# robot.net
KiCad netlist of a schematic drawn in EAGLE
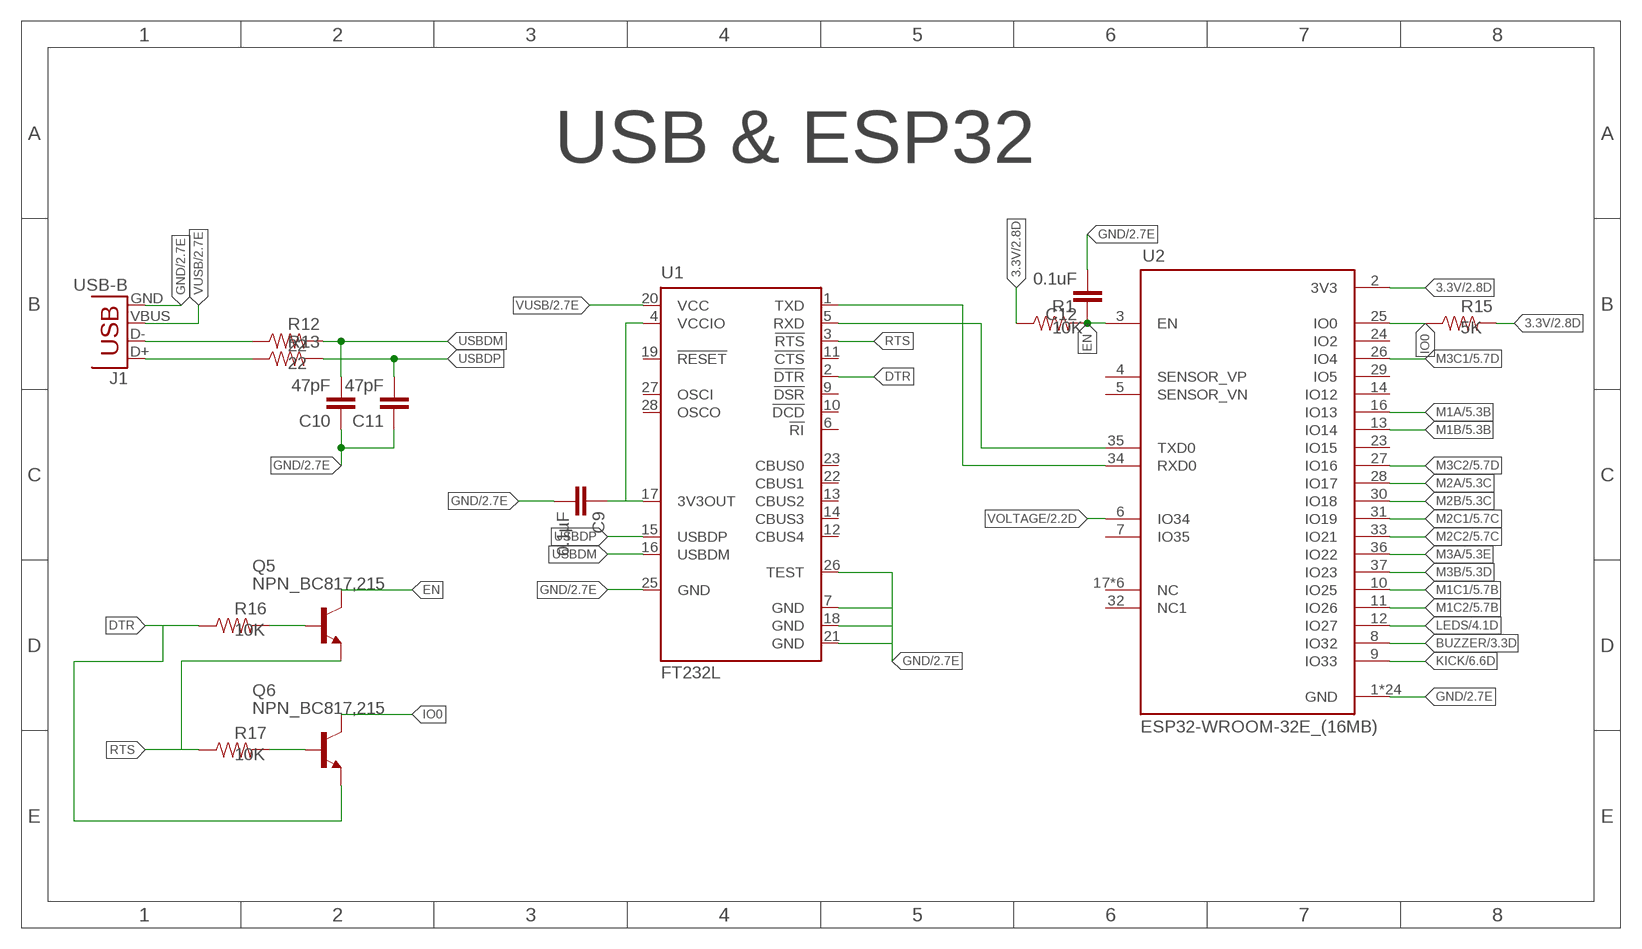
[diagram p0: schematic, sheet 1]
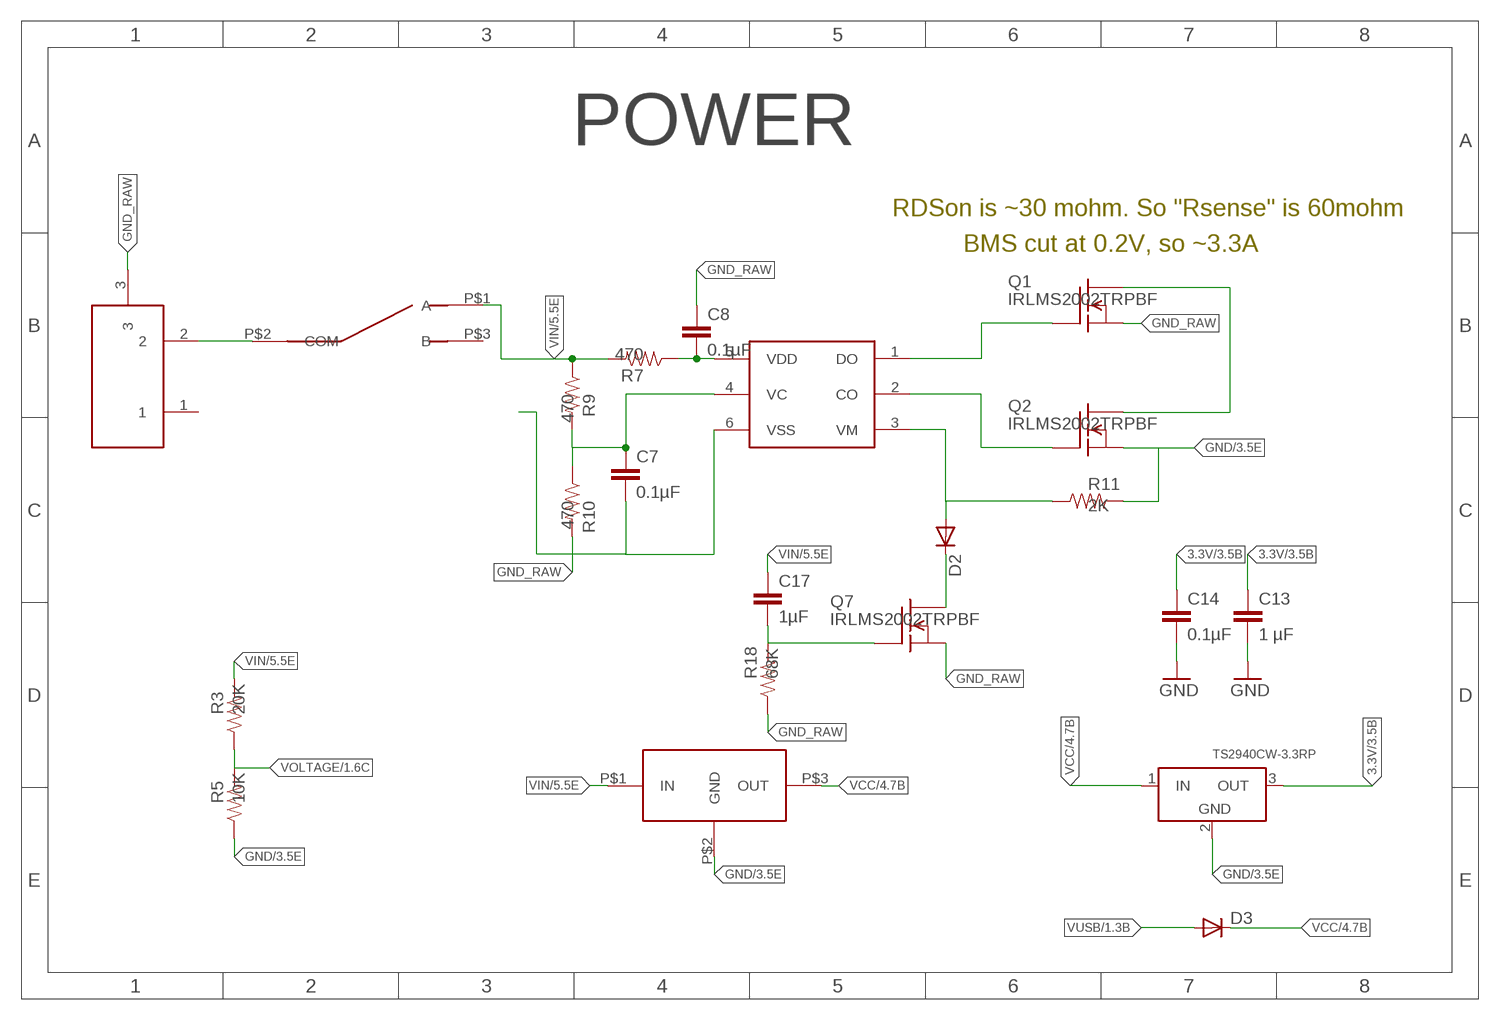
[diagram p1: schematic, sheet 2]
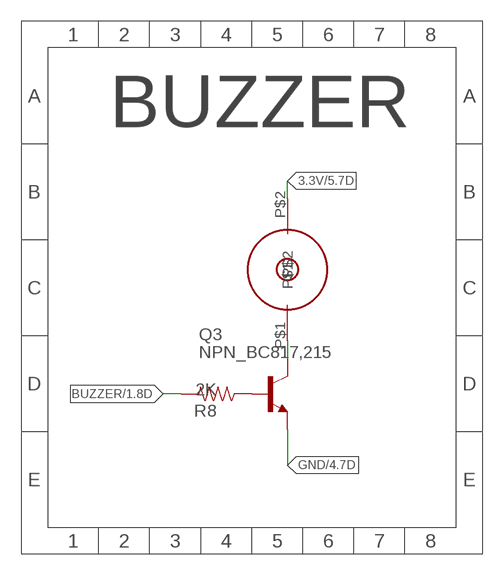
[diagram p2: schematic, sheet 3]
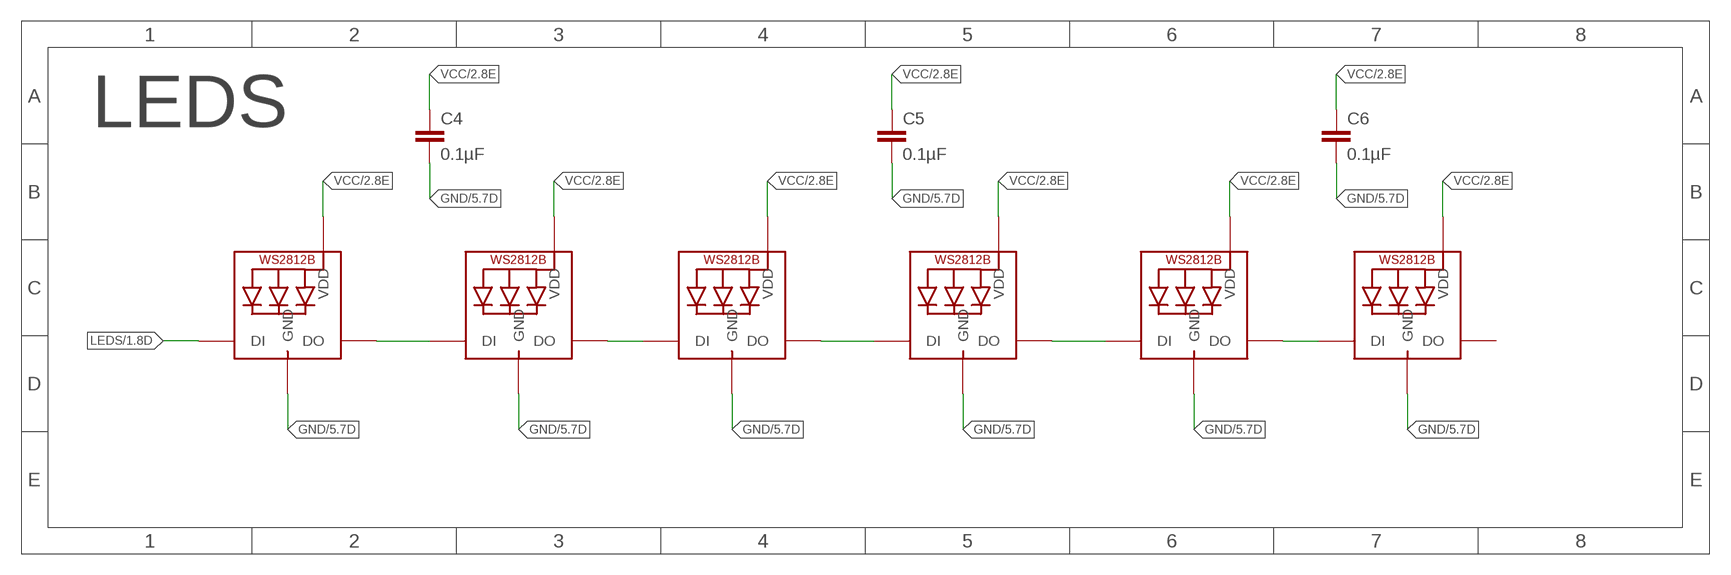
[diagram p3: schematic, sheet 4]
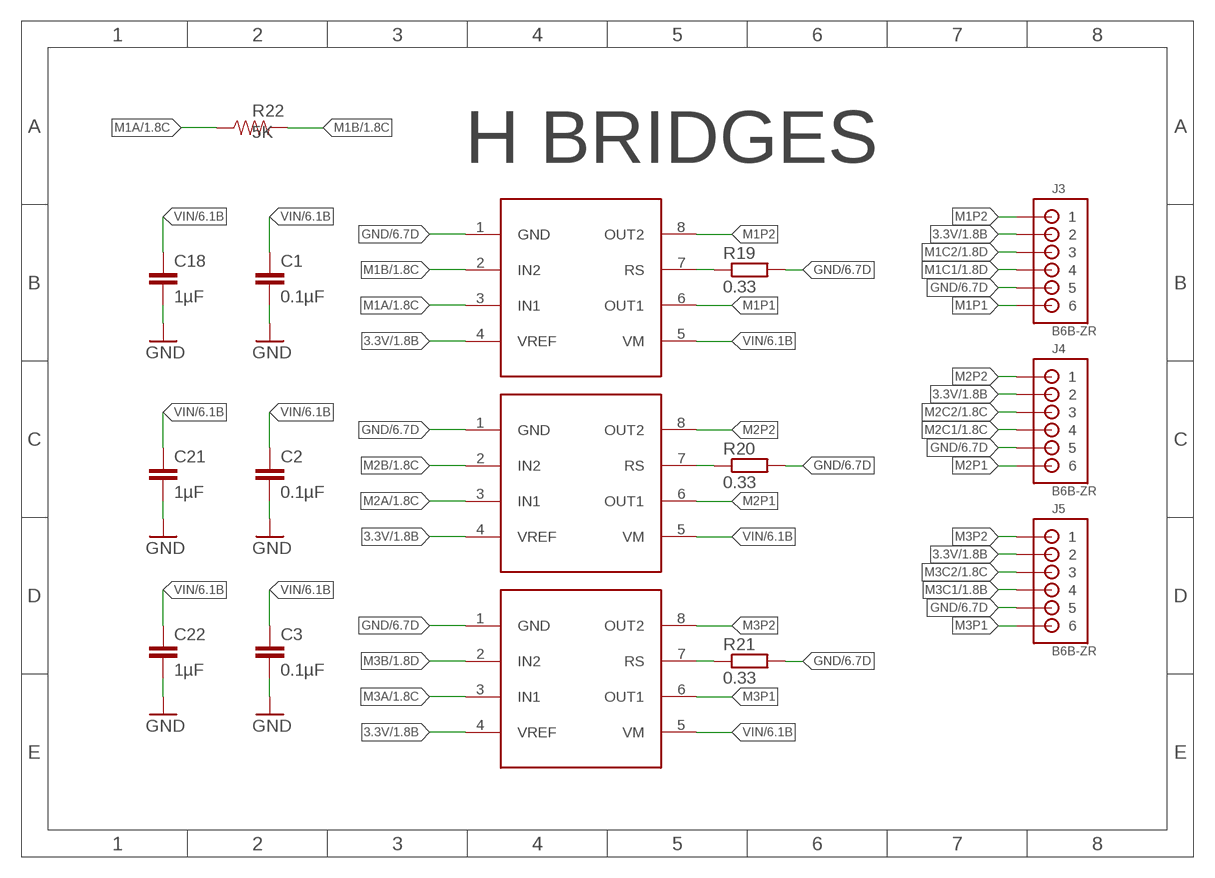
[diagram p4: schematic, sheet 5]
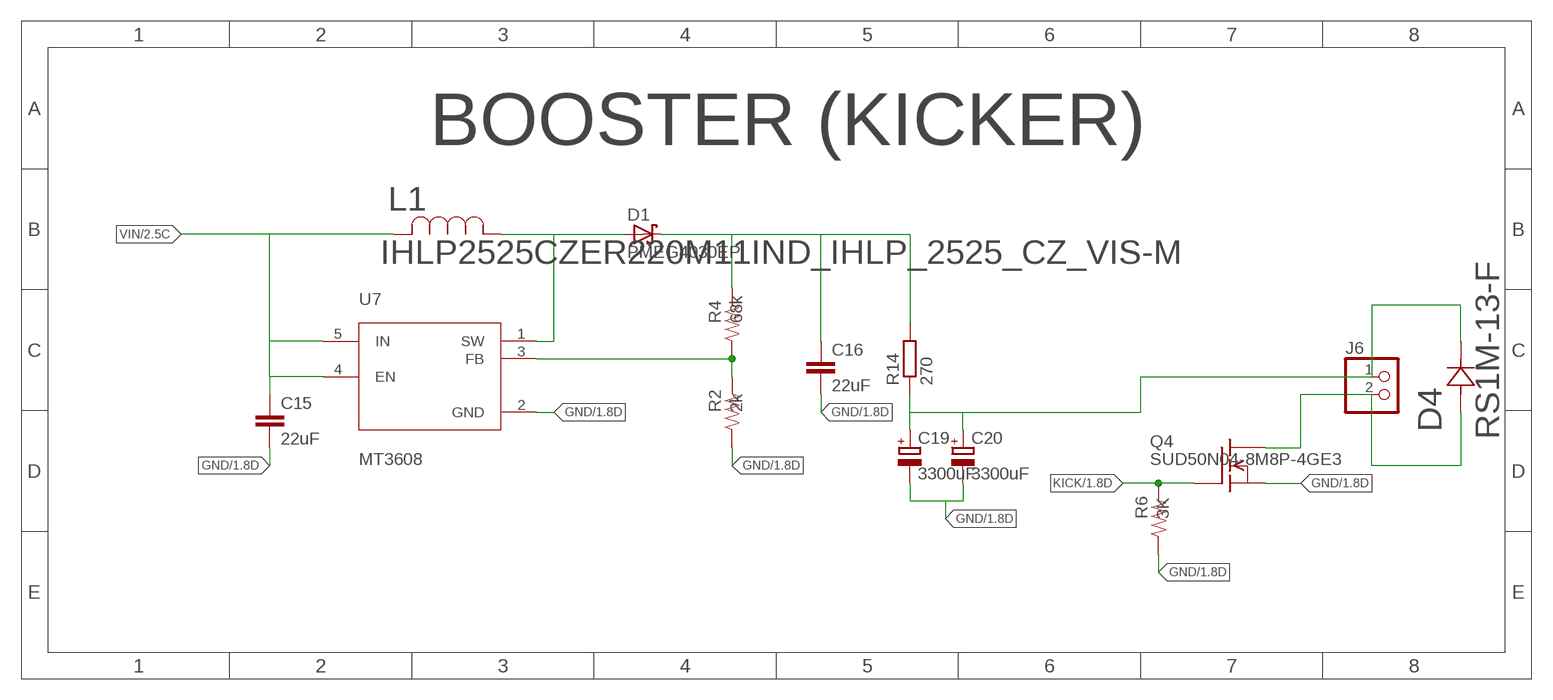
[diagram p5: schematic, sheet 6]

(export (version "E")
  (design (tool "Eeschema 10.0.6"))
  (components
    (comp (ref "C9")
      (value "0.1µF")
      (footprint "eagle-import:0805")
      (libsource (lib "eagle-import") (part "0.33UF/330NF-0805-50V-10%"))
    )
    (comp (ref "C10")
      (value "47pF")
      (footprint "eagle-import:0805")
      (libsource (lib "eagle-import") (part "CAP0805"))
    )
    (comp (ref "C11")
      (value "47pF")
      (footprint "eagle-import:0805")
      (libsource (lib "eagle-import") (part "CAP0805"))
    )
    (comp (ref "C12")
      (value "0.1uF")
      (footprint "eagle-import:0805")
      (libsource (lib "eagle-import") (part "CAP0805"))
    )
    (comp (ref "J1")
      (value "USB-B")
      (footprint "eagle-import:USB-B-PTH")
      (libsource (lib "eagle-import") (part "USBPTH"))
    )
    (comp (ref "Q5")
      (value "NPN_BC817,215")
      (footprint "eagle-import:SOT-23")
      (libsource (lib "eagle-import") (part "NPN_BC817,215"))
    )
    (comp (ref "Q6")
      (value "NPN_BC817,215")
      (footprint "eagle-import:SOT-23")
      (libsource (lib "eagle-import") (part "NPN_BC817,215"))
    )
    (comp (ref "R1")
      (value "10K")
      (footprint "eagle-import:0805")
      (fields (field (name "PROD_ID") "RES-11622"))
      (libsource (lib "eagle-import") (part "0.3OHM-0805-1/8W-1%"))
    )
    (comp (ref "R12")
      (value "22")
      (footprint "eagle-import:0805")
      (libsource (lib "eagle-import") (part "0.3OHM-0805-1/8W-1%"))
    )
    (comp (ref "R13")
      (value "22")
      (footprint "eagle-import:0805")
      (fields (field (name "PROD_ID") "RES-11622"))
      (libsource (lib "eagle-import") (part "0.3OHM-0805-1/8W-1%"))
    )
    (comp (ref "R15")
      (value "5K")
      (footprint "eagle-import:0805")
      (fields (field (name "PROD_ID") "RES-11622"))
      (libsource (lib "eagle-import") (part "0.3OHM-0805-1/8W-1%"))
    )
    (comp (ref "R16")
      (value "10K")
      (footprint "eagle-import:0805")
      (fields (field (name "PROD_ID") "RES-11622"))
      (libsource (lib "eagle-import") (part "0.3OHM-0805-1/8W-1%"))
    )
    (comp (ref "R17")
      (value "10K")
      (footprint "eagle-import:0805")
      (fields (field (name "PROD_ID") "RES-11622"))
      (libsource (lib "eagle-import") (part "0.3OHM-0805-1/8W-1%"))
    )
    (comp (ref "U1")
      (value "FT232L")
      (footprint "eagle-import:SSOP28")
      (fields (field (name "MPN") "FT232RL"))
      (libsource (lib "eagle-import") (part "FT232L"))
    )
    (comp (ref "U2")
      (value "ESP32-WROOM-32E_(16MB)")
      (footprint "eagle-import:MODULE_ESP32-WROOM-32E_(16MB)")
      (fields (field (name "MF") "Espressif Systems") (field (name "MP") "ESP32-WROOM-32E (16MB)"))
      (libsource (lib "eagle-import") (part "ESP32-WROOM-32E_(16MB)"))
    )
    (comp (ref "C7")
      (value "0.1µF")
      (footprint "eagle-import:0805")
      (libsource (lib "eagle-import") (part "0.33UF/330NF-0805-50V-10%"))
    )
    (comp (ref "C8")
      (value "0.1µF")
      (footprint "eagle-import:0805")
      (fields (field (name "PROD_ID") "CAP-08469"))
      (libsource (lib "eagle-import") (part "0.33UF/330NF-0805-50V-10%"))
    )
    (comp (ref "C13")
      (value "1 µF")
      (footprint "eagle-import:0805")
      (fields (field (name "PROD_ID") "CAP-08469"))
      (libsource (lib "eagle-import") (part "0.33UF/330NF-0805-50V-10%"))
    )
    (comp (ref "C14")
      (value "0.1µF")
      (footprint "eagle-import:0805")
      (fields (field (name "PROD_ID") "CAP-08469"))
      (libsource (lib "eagle-import") (part "0.33UF/330NF-0805-50V-10%"))
    )
    (comp (ref "C17")
      (value "1µF")
      (footprint "eagle-import:0805")
      (fields (field (name "PROD_ID") "CAP-08469"))
      (libsource (lib "eagle-import") (part "0.33UF/330NF-0805-50V-10%"))
    )
    (comp (ref "D2")
      (value "DIODESOD")
      (footprint "eagle-import:SOD-323")
      (libsource (lib "eagle-import") (part "DIODESOD"))
    )
    (comp (ref "D3")
      (value "DIODESOD")
      (footprint "eagle-import:SOD-323")
      (libsource (lib "eagle-import") (part "DIODESOD"))
    )
    (comp (ref "J2")
      (value "DC21MMX")
      (footprint "eagle-import:DC-21MM")
      (libsource (lib "eagle-import") (part "DC21MMX"))
    )
    (comp (ref "Q1")
      (value "IRLMS2002TRPBF")
      (footprint "eagle-import:SOT23-6")
      (libsource (lib "eagle-import") (part "IRLMS2002TRPBF"))
    )
    (comp (ref "Q2")
      (value "IRLMS2002TRPBF")
      (footprint "eagle-import:SOT23-6")
      (libsource (lib "eagle-import") (part "IRLMS2002TRPBF"))
    )
    (comp (ref "Q7")
      (value "IRLMS2002TRPBF")
      (footprint "eagle-import:SOT23-6")
      (libsource (lib "eagle-import") (part "IRLMS2002TRPBF"))
    )
    (comp (ref "R3")
      (value "20K")
      (footprint "eagle-import:0805")
      (libsource (lib "eagle-import") (part "0.3OHM-0805-1/8W-1%"))
    )
    (comp (ref "R5")
      (value "10K")
      (footprint "eagle-import:0805")
      (libsource (lib "eagle-import") (part "0.3OHM-0805-1/8W-1%"))
    )
    (comp (ref "R7")
      (value "470")
      (footprint "eagle-import:0805")
      (libsource (lib "eagle-import") (part "0.3OHM-0805-1/8W-1%"))
    )
    (comp (ref "R9")
      (value "470")
      (footprint "eagle-import:0805")
      (libsource (lib "eagle-import") (part "0.3OHM-0805-1/8W-1%"))
    )
    (comp (ref "R10")
      (value "470")
      (footprint "eagle-import:0805")
      (libsource (lib "eagle-import") (part "0.3OHM-0805-1/8W-1%"))
    )
    (comp (ref "R11")
      (value "2K")
      (footprint "eagle-import:0805")
      (libsource (lib "eagle-import") (part "0.3OHM-0805-1/8W-1%"))
    )
    (comp (ref "R18")
      (value "68K")
      (footprint "eagle-import:0805")
      (fields (field (name "PROD_ID") "RES-11622"))
      (libsource (lib "eagle-import") (part "0.3OHM-0805-1/8W-1%"))
    )
    (comp (ref "REG1")
      (value "REG_5V")
      (footprint "eagle-import:TRACOPOWER")
      (libsource (lib "eagle-import") (part "REG_5V"))
    )
    (comp (ref "SW1")
      (value "L102011ML04Q")
      (footprint "eagle-import:L102011ML04Q")
      (libsource (lib "eagle-import") (part "L102011ML04Q"))
    )
    (comp (ref "U3")
      (value "S8252")
      (footprint "eagle-import:SOT23-6")
      (libsource (lib "eagle-import") (part "S8252"))
    )
    (comp (ref "U8")
      (value "TS2940CW-3.3RP")
      (footprint "eagle-import:SOT223")
      (libsource (lib "eagle-import") (part "TS2940CW-3.3RP"))
    )
    (comp (ref "C15")
      (value "22uF")
      (footprint "eagle-import:C0805")
      (libsource (lib "eagle-import") (part "C-EUC0805"))
    )
    (comp (ref "C16")
      (value "22uF")
      (footprint "eagle-import:C0805")
      (libsource (lib "eagle-import") (part "C-EUC0805"))
    )
    (comp (ref "C19")
      (value "3300uF")
      (footprint "eagle-import:E5-13")
      (libsource (lib "eagle-import") (part "CPOL-EUE5-13"))
    )
    (comp (ref "C20")
      (value "3300uF")
      (footprint "eagle-import:E5-13")
      (libsource (lib "eagle-import") (part "CPOL-EUE5-13"))
    )
    (comp (ref "D1")
      (value "PMEG4030EP")
      (footprint "eagle-import:SOD128")
      (libsource (lib "eagle-import") (part "PMEG4030EP"))
    )
    (comp (ref "D4")
      (value "RS1M-13-F")
      (footprint "eagle-import:RS1M")
      (libsource (lib "eagle-import") (part "RS1M-13-F"))
    )
    (comp (ref "J6")
      (value "RHOBAN_KICKER")
      (footprint "eagle-import:RHOBAN_KICKER")
      (libsource (lib "eagle-import") (part "RHOBAN_KICKER"))
    )
    (comp (ref "L1")
      (value "IHLP2525CZER220M11IND_IHLP_2525_CZ_VIS-M")
      (footprint "eagle-import:IND_IHLP_2525_CZ_VIS-M")
      (fields (field (name "MANUFACTURER_PART_NUMBER") "IHLP2525CZER220M11"))
      (libsource (lib "eagle-import") (part "IHLP2525CZER220M11IND_IHLP_2525_CZ_VIS-M"))
    )
    (comp (ref "Q4")
      (value "SUD50N04-8M8P-4GE3")
      (footprint "eagle-import:TO252")
      (libsource (lib "eagle-import") (part "SUD50N04-8M8P-4GE3"))
    )
    (comp (ref "R2")
      (value "2k")
      (footprint "eagle-import:0805")
      (libsource (lib "eagle-import") (part "0.3OHM-0805-1/8W-1%"))
    )
    (comp (ref "R4")
      (value "68k")
      (footprint "eagle-import:0805")
      (libsource (lib "eagle-import") (part "0.3OHM-0805-1/8W-1%"))
    )
    (comp (ref "R6")
      (value "3K")
      (footprint "eagle-import:0805")
      (fields (field (name "PROD_ID") "RES-11622"))
      (libsource (lib "eagle-import") (part "0.3OHM-0805-1/8W-1%"))
    )
    (comp (ref "R14")
      (value "270")
      (footprint "eagle-import:R2010")
      (libsource (lib "eagle-import") (part "R-EU_R2010"))
    )
    (comp (ref "U7")
      (value "MT3608")
      (footprint "eagle-import:SOT95P280X145-6N")
      (fields (field (name "MF") "Aerosemi Technology Co., Ltd"))
      (libsource (lib "eagle-import") (part "MT3608"))
    )
    (comp (ref "B1")
      (value "BUZZER66")
      (footprint "eagle-import:BUZZER66")
      (libsource (lib "eagle-import") (part "BUZZER66"))
    )
    (comp (ref "Q3")
      (value "NPN_BC817,215")
      (footprint "eagle-import:SOT-23")
      (libsource (lib "eagle-import") (part "NPN_BC817,215"))
    )
    (comp (ref "R8")
      (value "2K")
      (footprint "eagle-import:0805")
      (libsource (lib "eagle-import") (part "0.3OHM-0805-1/8W-1%"))
    )
    (comp (ref "C1")
      (value "0.1µF")
      (footprint "eagle-import:0805")
      (libsource (lib "eagle-import") (part "0.33UF/330NF-0805-50V-10%"))
    )
    (comp (ref "C2")
      (value "0.1µF")
      (footprint "eagle-import:0805")
      (fields (field (name "PROD_ID") "CAP-08469"))
      (libsource (lib "eagle-import") (part "0.33UF/330NF-0805-50V-10%"))
    )
    (comp (ref "C3")
      (value "0.1µF")
      (footprint "eagle-import:0805")
      (fields (field (name "PROD_ID") "CAP-08469"))
      (libsource (lib "eagle-import") (part "0.33UF/330NF-0805-50V-10%"))
    )
    (comp (ref "C18")
      (value "1µF")
      (footprint "eagle-import:0805")
      (libsource (lib "eagle-import") (part "0.33UF/330NF-0805-50V-10%"))
    )
    (comp (ref "C21")
      (value "1µF")
      (footprint "eagle-import:0805")
      (fields (field (name "PROD_ID") "CAP-08469"))
      (libsource (lib "eagle-import") (part "0.33UF/330NF-0805-50V-10%"))
    )
    (comp (ref "C22")
      (value "1µF")
      (footprint "eagle-import:0805")
      (fields (field (name "PROD_ID") "CAP-08469"))
      (libsource (lib "eagle-import") (part "0.33UF/330NF-0805-50V-10%"))
    )
    (comp (ref "J3")
      (value "B6B-ZR")
      (footprint "eagle-import:B6B-ZR")
      (libsource (lib "eagle-import") (part "B6B-ZR"))
    )
    (comp (ref "J4")
      (value "B6B-ZR")
      (footprint "eagle-import:B6B-ZR")
      (libsource (lib "eagle-import") (part "B6B-ZR"))
    )
    (comp (ref "J5")
      (value "B6B-ZR")
      (footprint "eagle-import:B6B-ZR")
      (libsource (lib "eagle-import") (part "B6B-ZR"))
    )
    (comp (ref "R19")
      (value "0.33")
      (footprint "eagle-import:R1206")
      (libsource (lib "eagle-import") (part "R-EU_R1206"))
    )
    (comp (ref "R20")
      (value "0.33")
      (footprint "eagle-import:R1206")
      (libsource (lib "eagle-import") (part "R-EU_R1206"))
    )
    (comp (ref "R21")
      (value "0.33")
      (footprint "eagle-import:R1206")
      (libsource (lib "eagle-import") (part "R-EU_R1206"))
    )
    (comp (ref "R22")
      (value "5K")
      (footprint "eagle-import:0805")
      (fields (field (name "PROD_ID") "RES-11622"))
      (libsource (lib "eagle-import") (part "0.3OHM-0805-1/8W-1%"))
    )
    (comp (ref "U10")
      (value "TB67H450FNG")
      (footprint "eagle-import:HSOP8")
      (libsource (lib "eagle-import") (part "TB67H450FNG"))
    )
    (comp (ref "U11")
      (value "TB67H450FNG")
      (footprint "eagle-import:HSOP8")
      (libsource (lib "eagle-import") (part "TB67H450FNG"))
    )
    (comp (ref "U12")
      (value "TB67H450FNG")
      (footprint "eagle-import:HSOP8")
      (libsource (lib "eagle-import") (part "TB67H450FNG"))
    )
    (comp (ref "C4")
      (value "0.1µF")
      (footprint "eagle-import:0805")
      (libsource (lib "eagle-import") (part "0.33UF/330NF-0805-50V-10%"))
    )
    (comp (ref "C5")
      (value "0.1µF")
      (footprint "eagle-import:0805")
      (fields (field (name "PROD_ID") "CAP-08469"))
      (libsource (lib "eagle-import") (part "0.33UF/330NF-0805-50V-10%"))
    )
    (comp (ref "C6")
      (value "0.1µF")
      (footprint "eagle-import:0805")
      (fields (field (name "PROD_ID") "CAP-08469"))
      (libsource (lib "eagle-import") (part "0.33UF/330NF-0805-50V-10%"))
    )
    (comp (ref "LED1")
      (value "WS2812B5050")
      (footprint "eagle-import:WS2812B")
      (libsource (lib "eagle-import") (part "WS2812B5050"))
    )
    (comp (ref "LED2")
      (value "WS2812B5050")
      (footprint "eagle-import:WS2812B")
      (libsource (lib "eagle-import") (part "WS2812B5050"))
    )
    (comp (ref "LED3")
      (value "WS2812B5050")
      (footprint "eagle-import:WS2812B")
      (libsource (lib "eagle-import") (part "WS2812B5050"))
    )
    (comp (ref "LED4")
      (value "WS2812B5050")
      (footprint "eagle-import:WS2812B")
      (libsource (lib "eagle-import") (part "WS2812B5050"))
    )
    (comp (ref "LED5")
      (value "WS2812B5050")
      (footprint "eagle-import:WS2812B")
      (libsource (lib "eagle-import") (part "WS2812B5050"))
    )
    (comp (ref "LED6")
      (value "WS2812B5050")
      (footprint "eagle-import:WS2812B")
      (libsource (lib "eagle-import") (part "WS2812B5050"))
    )
  )
  (nets
    (net (code "1") (name "1") (class "Default")
      (node (ref "J2") (pin "1") (pinfunction "1_1") (pintype "power_in"))
    )
    (net (code "2") (name "3.3V") (class "Default")
      (node (ref "B1") (pin "P$2") (pinfunction "P$2_P$2") (pintype "bidirectional"))
      (node (ref "C13") (pin "1") (pinfunction "1_1") (pintype "passive"))
      (node (ref "C14") (pin "1") (pinfunction "1_1") (pintype "passive"))
      (node (ref "J3") (pin "2") (pinfunction "2_2") (pintype "bidirectional"))
      (node (ref "J4") (pin "2") (pinfunction "2_2") (pintype "bidirectional"))
      (node (ref "J5") (pin "2") (pinfunction "2_2") (pintype "bidirectional"))
      (node (ref "R1") (pin "1") (pinfunction "1_1") (pintype "passive"))
      (node (ref "R15") (pin "2") (pinfunction "2_2") (pintype "passive"))
      (node (ref "U10") (pin "4") (pinfunction "VREF_4") (pintype "bidirectional"))
      (node (ref "U11") (pin "4") (pinfunction "VREF_4") (pintype "bidirectional"))
      (node (ref "U12") (pin "4") (pinfunction "VREF_4") (pintype "bidirectional"))
      (node (ref "U2") (pin "2") (pinfunction "3V3_2") (pintype "power_in"))
      (node (ref "U8") (pin "3") (pinfunction "OUT_3") (pintype "output"))
    )
    (net (code "3") (name "BUZZER") (class "Default")
      (node (ref "R8") (pin "2") (pinfunction "2_2") (pintype "passive"))
      (node (ref "U2") (pin "8") (pinfunction "IO32_8") (pintype "bidirectional"))
    )
    (net (code "4") (name "DTR") (class "Default")
      (node (ref "Q6") (pin "2") (pinfunction "E_2") (pintype "passive"))
      (node (ref "R16") (pin "1") (pinfunction "1_1") (pintype "passive"))
      (node (ref "U1") (pin "2") (pinfunction "~{DTR}_2") (pintype "output"))
    )
    (net (code "5") (name "EN") (class "Default")
      (node (ref "C12") (pin "1") (pinfunction "1_1") (pintype "passive"))
      (node (ref "Q5") (pin "3") (pinfunction "C_3") (pintype "passive"))
      (node (ref "R1") (pin "2") (pinfunction "2_2") (pintype "passive"))
      (node (ref "U2") (pin "3") (pinfunction "EN_3") (pintype "input"))
    )
    (net (code "6") (name "GND") (class "Default")
      (node (ref "C1") (pin "2") (pinfunction "2_2") (pintype "passive"))
      (node (ref "C10") (pin "1") (pinfunction "1_1") (pintype "passive"))
      (node (ref "C11") (pin "1") (pinfunction "1_1") (pintype "passive"))
      (node (ref "C12") (pin "2") (pinfunction "2_2") (pintype "passive"))
      (node (ref "C13") (pin "2") (pinfunction "2_2") (pintype "passive"))
      (node (ref "C14") (pin "2") (pinfunction "2_2") (pintype "passive"))
      (node (ref "C15") (pin "2") (pinfunction "2_2") (pintype "passive"))
      (node (ref "C16") (pin "2") (pinfunction "2_2") (pintype "passive"))
      (node (ref "C18") (pin "2") (pinfunction "2_2") (pintype "passive"))
      (node (ref "C19") (pin "-") (pinfunction "-_-") (pintype "passive"))
      (node (ref "C2") (pin "2") (pinfunction "2_2") (pintype "passive"))
      (node (ref "C20") (pin "-") (pinfunction "-_-") (pintype "passive"))
      (node (ref "C21") (pin "2") (pinfunction "2_2") (pintype "passive"))
      (node (ref "C22") (pin "2") (pinfunction "2_2") (pintype "passive"))
      (node (ref "C3") (pin "2") (pinfunction "2_2") (pintype "passive"))
      (node (ref "C4") (pin "2") (pinfunction "2_2") (pintype "passive"))
      (node (ref "C5") (pin "2") (pinfunction "2_2") (pintype "passive"))
      (node (ref "C6") (pin "2") (pinfunction "2_2") (pintype "passive"))
      (node (ref "C9") (pin "2") (pinfunction "2_2") (pintype "passive"))
      (node (ref "J1") (pin "GND") (pinfunction "GND_GND") (pintype "bidirectional"))
      (node (ref "J3") (pin "5") (pinfunction "5_5") (pintype "bidirectional"))
      (node (ref "J4") (pin "5") (pinfunction "5_5") (pintype "bidirectional"))
      (node (ref "J5") (pin "5") (pinfunction "5_5") (pintype "bidirectional"))
      (node (ref "LED1") (pin "3-GND") (pinfunction "GND_3-GND") (pintype "power_in"))
      (node (ref "LED2") (pin "3-GND") (pinfunction "GND_3-GND") (pintype "power_in"))
      (node (ref "LED3") (pin "3-GND") (pinfunction "GND_3-GND") (pintype "power_in"))
      (node (ref "LED4") (pin "3-GND") (pinfunction "GND_3-GND") (pintype "power_in"))
      (node (ref "LED5") (pin "3-GND") (pinfunction "GND_3-GND") (pintype "power_in"))
      (node (ref "LED6") (pin "3-GND") (pinfunction "GND_3-GND") (pintype "power_in"))
      (node (ref "Q2") (pin "4") (pinfunction "S_4") (pintype "passive"))
      (node (ref "Q3") (pin "2") (pinfunction "E_2") (pintype "passive"))
      (node (ref "Q4") (pin "2") (pinfunction "S_2") (pintype "passive"))
      (node (ref "R11") (pin "2") (pinfunction "2_2") (pintype "passive"))
      (node (ref "R19") (pin "2") (pinfunction "2_2") (pintype "passive"))
      (node (ref "R2") (pin "1") (pinfunction "1_1") (pintype "passive"))
      (node (ref "R20") (pin "2") (pinfunction "2_2") (pintype "passive"))
      (node (ref "R21") (pin "2") (pinfunction "2_2") (pintype "passive"))
      (node (ref "R5") (pin "1") (pinfunction "1_1") (pintype "passive"))
      (node (ref "R6") (pin "1") (pinfunction "1_1") (pintype "passive"))
      (node (ref "REG1") (pin "P$2") (pinfunction "GND_P$2") (pintype "bidirectional"))
      (node (ref "U1") (pin "18") (pinfunction "GND_18") (pintype "power_in"))
      (node (ref "U1") (pin "21") (pinfunction "GND_21") (pintype "power_in"))
      (node (ref "U1") (pin "25") (pinfunction "GND_25") (pintype "power_in"))
      (node (ref "U1") (pin "26") (pinfunction "TEST_26") (pintype "input"))
      (node (ref "U1") (pin "7") (pinfunction "GND_7") (pintype "power_in"))
      (node (ref "U10") (pin "1") (pinfunction "GND_1") (pintype "bidirectional"))
      (node (ref "U11") (pin "1") (pinfunction "GND_1") (pintype "bidirectional"))
      (node (ref "U12") (pin "1") (pinfunction "GND_1") (pintype "bidirectional"))
      (node (ref "U2") (pin "1") (pinfunction "GND_1") (pintype "power_in"))
      (node (ref "U2") (pin "15") (pinfunction "GND_15") (pintype "power_in"))
      (node (ref "U2") (pin "38") (pinfunction "GND_38") (pintype "power_in"))
      (node (ref "U2") (pin "39_1") (pinfunction "GND_39_1") (pintype "power_in"))
      (node (ref "U2") (pin "39_10") (pinfunction "GND_39_10") (pintype "power_in"))
      (node (ref "U2") (pin "39_11") (pinfunction "GND_39_11") (pintype "power_in"))
      (node (ref "U2") (pin "39_12") (pinfunction "GND_39_12") (pintype "power_in"))
      (node (ref "U2") (pin "39_13") (pinfunction "GND_39_13") (pintype "power_in"))
      (node (ref "U2") (pin "39_14") (pinfunction "GND_39_14") (pintype "power_in"))
      (node (ref "U2") (pin "39_15") (pinfunction "GND_39_15") (pintype "power_in"))
      (node (ref "U2") (pin "39_16") (pinfunction "GND_39_16") (pintype "power_in"))
      (node (ref "U2") (pin "39_17") (pinfunction "GND_39_17") (pintype "power_in"))
      (node (ref "U2") (pin "39_18") (pinfunction "GND_39_18") (pintype "power_in"))
      (node (ref "U2") (pin "39_19") (pinfunction "GND_39_19") (pintype "power_in"))
      (node (ref "U2") (pin "39_2") (pinfunction "GND_39_2") (pintype "power_in"))
      (node (ref "U2") (pin "39_20") (pinfunction "GND_39_20") (pintype "power_in"))
      (node (ref "U2") (pin "39_21") (pinfunction "GND_39_21") (pintype "power_in"))
      (node (ref "U2") (pin "39_3") (pinfunction "GND_39_3") (pintype "power_in"))
      (node (ref "U2") (pin "39_4") (pinfunction "GND_39_4") (pintype "power_in"))
      (node (ref "U2") (pin "39_5") (pinfunction "GND_39_5") (pintype "power_in"))
      (node (ref "U2") (pin "39_6") (pinfunction "GND_39_6") (pintype "power_in"))
      (node (ref "U2") (pin "39_7") (pinfunction "GND_39_7") (pintype "power_in"))
      (node (ref "U2") (pin "39_8") (pinfunction "GND_39_8") (pintype "power_in"))
      (node (ref "U2") (pin "39_9") (pinfunction "GND_39_9") (pintype "power_in"))
      (node (ref "U7") (pin "2") (pinfunction "GND_2") (pintype "power_in"))
      (node (ref "U8") (pin "2") (pinfunction "GND_2") (pintype "power_in"))
    )
    (net (code "7") (name "GND_RAW") (class "Default")
      (node (ref "C7") (pin "2") (pinfunction "2_2") (pintype "passive"))
      (node (ref "C8") (pin "1") (pinfunction "1_1") (pintype "passive"))
      (node (ref "J2") (pin "3") (pinfunction "3_3") (pintype "power_in"))
      (node (ref "Q1") (pin "4") (pinfunction "S_4") (pintype "passive"))
      (node (ref "Q7") (pin "4") (pinfunction "S_4") (pintype "passive"))
      (node (ref "R10") (pin "2") (pinfunction "2_2") (pintype "passive"))
      (node (ref "R18") (pin "1") (pinfunction "1_1") (pintype "passive"))
      (node (ref "U3") (pin "6") (pinfunction "VSS_6") (pintype "passive"))
    )
    (net (code "8") (name "IO0") (class "Default")
      (node (ref "Q6") (pin "3") (pinfunction "C_3") (pintype "passive"))
      (node (ref "R15") (pin "1") (pinfunction "1_1") (pintype "passive"))
      (node (ref "U2") (pin "25") (pinfunction "IO0_25") (pintype "bidirectional"))
    )
    (net (code "9") (name "KICK") (class "Default")
      (node (ref "Q4") (pin "1") (pinfunction "G_1") (pintype "passive"))
      (node (ref "R6") (pin "2") (pinfunction "2_2") (pintype "passive"))
      (node (ref "U2") (pin "9") (pinfunction "IO33_9") (pintype "bidirectional"))
    )
    (net (code "10") (name "LEDS") (class "Default")
      (node (ref "LED1") (pin "4-DIN") (pinfunction "DI_4-DIN") (pintype "input"))
      (node (ref "U2") (pin "12") (pinfunction "IO27_12") (pintype "bidirectional"))
    )
    (net (code "11") (name "M1A") (class "Default")
      (node (ref "R22") (pin "1") (pinfunction "1_1") (pintype "passive"))
      (node (ref "U10") (pin "3") (pinfunction "IN1_3") (pintype "bidirectional"))
      (node (ref "U2") (pin "16") (pinfunction "IO13_16") (pintype "bidirectional"))
    )
    (net (code "12") (name "M1B") (class "Default")
      (node (ref "R22") (pin "2") (pinfunction "2_2") (pintype "passive"))
      (node (ref "U10") (pin "2") (pinfunction "IN2_2") (pintype "bidirectional"))
      (node (ref "U2") (pin "13") (pinfunction "IO14_13") (pintype "bidirectional"))
    )
    (net (code "13") (name "M1C1") (class "Default")
      (node (ref "J3") (pin "4") (pinfunction "4_4") (pintype "bidirectional"))
      (node (ref "U2") (pin "10") (pinfunction "IO25_10") (pintype "bidirectional"))
    )
    (net (code "14") (name "M1C2") (class "Default")
      (node (ref "J3") (pin "3") (pinfunction "3_3") (pintype "bidirectional"))
      (node (ref "U2") (pin "11") (pinfunction "IO26_11") (pintype "bidirectional"))
    )
    (net (code "15") (name "M1P1") (class "Default")
      (node (ref "J3") (pin "6") (pinfunction "6_6") (pintype "bidirectional"))
      (node (ref "U10") (pin "6") (pinfunction "OUT1_6") (pintype "bidirectional"))
    )
    (net (code "16") (name "M1P2") (class "Default")
      (node (ref "J3") (pin "1") (pinfunction "1_1") (pintype "bidirectional"))
      (node (ref "U10") (pin "8") (pinfunction "OUT2_8") (pintype "bidirectional"))
    )
    (net (code "17") (name "M2A") (class "Default")
      (node (ref "U11") (pin "3") (pinfunction "IN1_3") (pintype "bidirectional"))
      (node (ref "U2") (pin "28") (pinfunction "IO17_28") (pintype "bidirectional"))
    )
    (net (code "18") (name "M2B") (class "Default")
      (node (ref "U11") (pin "2") (pinfunction "IN2_2") (pintype "bidirectional"))
      (node (ref "U2") (pin "30") (pinfunction "IO18_30") (pintype "bidirectional"))
    )
    (net (code "19") (name "M2C1") (class "Default")
      (node (ref "J4") (pin "4") (pinfunction "4_4") (pintype "bidirectional"))
      (node (ref "U2") (pin "31") (pinfunction "IO19_31") (pintype "bidirectional"))
    )
    (net (code "20") (name "M2C2") (class "Default")
      (node (ref "J4") (pin "3") (pinfunction "3_3") (pintype "bidirectional"))
      (node (ref "U2") (pin "33") (pinfunction "IO21_33") (pintype "bidirectional"))
    )
    (net (code "21") (name "M2P1") (class "Default")
      (node (ref "J4") (pin "6") (pinfunction "6_6") (pintype "bidirectional"))
      (node (ref "U11") (pin "6") (pinfunction "OUT1_6") (pintype "bidirectional"))
    )
    (net (code "22") (name "M2P2") (class "Default")
      (node (ref "J4") (pin "1") (pinfunction "1_1") (pintype "bidirectional"))
      (node (ref "U11") (pin "8") (pinfunction "OUT2_8") (pintype "bidirectional"))
    )
    (net (code "23") (name "M3A") (class "Default")
      (node (ref "U12") (pin "3") (pinfunction "IN1_3") (pintype "bidirectional"))
      (node (ref "U2") (pin "36") (pinfunction "IO22_36") (pintype "bidirectional"))
    )
    (net (code "24") (name "M3B") (class "Default")
      (node (ref "U12") (pin "2") (pinfunction "IN2_2") (pintype "bidirectional"))
      (node (ref "U2") (pin "37") (pinfunction "IO23_37") (pintype "bidirectional"))
    )
    (net (code "25") (name "M3C1") (class "Default")
      (node (ref "J5") (pin "4") (pinfunction "4_4") (pintype "bidirectional"))
      (node (ref "U2") (pin "26") (pinfunction "IO4_26") (pintype "bidirectional"))
    )
    (net (code "26") (name "M3C2") (class "Default")
      (node (ref "J5") (pin "3") (pinfunction "3_3") (pintype "bidirectional"))
      (node (ref "U2") (pin "27") (pinfunction "IO16_27") (pintype "bidirectional"))
    )
    (net (code "27") (name "M3P1") (class "Default")
      (node (ref "J5") (pin "6") (pinfunction "6_6") (pintype "bidirectional"))
      (node (ref "U12") (pin "6") (pinfunction "OUT1_6") (pintype "bidirectional"))
    )
    (net (code "28") (name "M3P2") (class "Default")
      (node (ref "J5") (pin "1") (pinfunction "1_1") (pintype "bidirectional"))
      (node (ref "U12") (pin "8") (pinfunction "OUT2_8") (pintype "bidirectional"))
    )
    (net (code "29") (name "Net-(C19-Pad+)") (class "Default")
      (node (ref "C19") (pin "+") (pinfunction "+_+") (pintype "passive"))
      (node (ref "C20") (pin "+") (pinfunction "+_+") (pintype "passive"))
      (node (ref "D4") (pin "K") (pinfunction "K_K") (pintype "passive"))
      (node (ref "J6") (pin "1") (pinfunction "1_1") (pintype "passive"))
      (node (ref "R14") (pin "1") (pinfunction "1_1") (pintype "passive"))
    )
    (net (code "30") (name "Net-(D1-A)") (class "Default")
      (node (ref "D1") (pin "2") (pinfunction "A_2") (pintype "passive"))
      (node (ref "L1") (pin "1") (pinfunction "1_1") (pintype "passive"))
      (node (ref "U7") (pin "1") (pinfunction "SW_1") (pintype "output"))
    )
    (net (code "31") (name "Net-(D1-K)") (class "Default")
      (node (ref "C16") (pin "1") (pinfunction "1_1") (pintype "passive"))
      (node (ref "D1") (pin "1") (pinfunction "K_1") (pintype "passive"))
      (node (ref "R14") (pin "2") (pinfunction "2_2") (pintype "passive"))
      (node (ref "R4") (pin "2") (pinfunction "2_2") (pintype "passive"))
    )
    (net (code "32") (name "Net-(D2-A)") (class "Default")
      (node (ref "D2") (pin "2") (pinfunction "A_2") (pintype "passive"))
      (node (ref "R11") (pin "1") (pinfunction "1_1") (pintype "passive"))
      (node (ref "U3") (pin "3") (pinfunction "VM_3") (pintype "passive"))
    )
    (net (code "33") (name "Net-(D2-C)") (class "Default")
      (node (ref "D2") (pin "1") (pinfunction "C_1") (pintype "passive"))
      (node (ref "Q7") (pin "1") (pinfunction "D_1") (pintype "passive"))
      (node (ref "Q7") (pin "2") (pinfunction "D_2") (pintype "passive"))
      (node (ref "Q7") (pin "5") (pinfunction "D_5") (pintype "passive"))
      (node (ref "Q7") (pin "6") (pinfunction "D_6") (pintype "passive"))
    )
    (net (code "34") (name "Net-(J1-PadD+)") (class "Default")
      (node (ref "J1") (pin "D+") (pinfunction "D+_D+") (pintype "bidirectional"))
      (node (ref "R13") (pin "1") (pinfunction "1_1") (pintype "passive"))
    )
    (net (code "35") (name "Net-(J1-PadD-)") (class "Default")
      (node (ref "J1") (pin "D-") (pinfunction "D-_D-") (pintype "bidirectional"))
      (node (ref "R12") (pin "1") (pinfunction "1_1") (pintype "passive"))
    )
    (net (code "36") (name "Net-(LED1-DO)") (class "Default")
      (node (ref "LED1") (pin "2-DOUT") (pinfunction "DO_2-DOUT") (pintype "output"))
      (node (ref "LED2") (pin "4-DIN") (pinfunction "DI_4-DIN") (pintype "input"))
    )
    (net (code "37") (name "Net-(LED2-DO)") (class "Default")
      (node (ref "LED2") (pin "2-DOUT") (pinfunction "DO_2-DOUT") (pintype "output"))
      (node (ref "LED3") (pin "4-DIN") (pinfunction "DI_4-DIN") (pintype "input"))
    )
    (net (code "38") (name "Net-(LED3-DO)") (class "Default")
      (node (ref "LED3") (pin "2-DOUT") (pinfunction "DO_2-DOUT") (pintype "output"))
      (node (ref "LED4") (pin "4-DIN") (pinfunction "DI_4-DIN") (pintype "input"))
    )
    (net (code "39") (name "Net-(LED4-DO)") (class "Default")
      (node (ref "LED4") (pin "2-DOUT") (pinfunction "DO_2-DOUT") (pintype "output"))
      (node (ref "LED5") (pin "4-DIN") (pinfunction "DI_4-DIN") (pintype "input"))
    )
    (net (code "40") (name "Net-(LED5-DO)") (class "Default")
      (node (ref "LED5") (pin "2-DOUT") (pinfunction "DO_2-DOUT") (pintype "output"))
      (node (ref "LED6") (pin "4-DIN") (pinfunction "DI_4-DIN") (pintype "input"))
    )
    (net (code "41") (name "Net-(Q1-D-Pad1)") (class "Default")
      (node (ref "Q1") (pin "1") (pinfunction "D_1") (pintype "passive"))
      (node (ref "Q1") (pin "2") (pinfunction "D_2") (pintype "passive"))
      (node (ref "Q1") (pin "5") (pinfunction "D_5") (pintype "passive"))
      (node (ref "Q1") (pin "6") (pinfunction "D_6") (pintype "passive"))
      (node (ref "Q2") (pin "1") (pinfunction "D_1") (pintype "passive"))
      (node (ref "Q2") (pin "2") (pinfunction "D_2") (pintype "passive"))
      (node (ref "Q2") (pin "5") (pinfunction "D_5") (pintype "passive"))
      (node (ref "Q2") (pin "6") (pinfunction "D_6") (pintype "passive"))
    )
    (net (code "42") (name "Net-(Q1-G)") (class "Default")
      (node (ref "Q1") (pin "3") (pinfunction "G_3") (pintype "passive"))
      (node (ref "U3") (pin "1") (pinfunction "DO_1") (pintype "passive"))
    )
    (net (code "43") (name "Net-(Q2-G)") (class "Default")
      (node (ref "Q2") (pin "3") (pinfunction "G_3") (pintype "passive"))
      (node (ref "U3") (pin "2") (pinfunction "CO_2") (pintype "passive"))
    )
    (net (code "44") (name "Net-(Q3-B)") (class "Default")
      (node (ref "Q3") (pin "1") (pinfunction "B_1") (pintype "passive"))
      (node (ref "R8") (pin "1") (pinfunction "1_1") (pintype "passive"))
    )
    (net (code "45") (name "Net-(Q3-C)") (class "Default")
      (node (ref "B1") (pin "P$1") (pinfunction "P$1_P$1") (pintype "bidirectional"))
      (node (ref "Q3") (pin "3") (pinfunction "C_3") (pintype "passive"))
    )
    (net (code "46") (name "Net-(Q4-D)") (class "Default")
      (node (ref "D4") (pin "A") (pinfunction "A_A") (pintype "passive"))
      (node (ref "J6") (pin "2") (pinfunction "2_2") (pintype "passive"))
      (node (ref "Q4") (pin "3") (pinfunction "D_3") (pintype "passive"))
    )
    (net (code "47") (name "Net-(Q5-B)") (class "Default")
      (node (ref "Q5") (pin "1") (pinfunction "B_1") (pintype "passive"))
      (node (ref "R16") (pin "2") (pinfunction "2_2") (pintype "passive"))
    )
    (net (code "48") (name "Net-(Q6-B)") (class "Default")
      (node (ref "Q6") (pin "1") (pinfunction "B_1") (pintype "passive"))
      (node (ref "R17") (pin "2") (pinfunction "2_2") (pintype "passive"))
    )
    (net (code "49") (name "Net-(Q7-G)") (class "Default")
      (node (ref "C17") (pin "2") (pinfunction "2_2") (pintype "passive"))
      (node (ref "Q7") (pin "3") (pinfunction "G_3") (pintype "passive"))
      (node (ref "R18") (pin "2") (pinfunction "2_2") (pintype "passive"))
    )
    (net (code "50") (name "Net-(SW1-COM)") (class "Default")
      (node (ref "J2") (pin "2") (pinfunction "2_2") (pintype "power_in"))
      (node (ref "SW1") (pin "P$2") (pinfunction "COM_P$2") (pintype "bidirectional"))
    )
    (net (code "51") (name "Net-(U1-3V3OUT)") (class "Default")
      (node (ref "C9") (pin "1") (pinfunction "1_1") (pintype "passive"))
      (node (ref "U1") (pin "17") (pinfunction "3V3OUT_17") (pintype "output"))
      (node (ref "U1") (pin "4") (pinfunction "VCCIO_4") (pintype "power_in"))
    )
    (net (code "52") (name "Net-(U1-RXD)") (class "Default")
      (node (ref "U1") (pin "5") (pinfunction "RXD_5") (pintype "input"))
      (node (ref "U2") (pin "35") (pinfunction "TXD0_35") (pintype "bidirectional"))
    )
    (net (code "53") (name "Net-(U1-TXD)") (class "Default")
      (node (ref "U1") (pin "1") (pinfunction "TXD_1") (pintype "output"))
      (node (ref "U2") (pin "34") (pinfunction "RXD0_34") (pintype "bidirectional"))
    )
    (net (code "54") (name "Net-(U3-VC)") (class "Default")
      (node (ref "C7") (pin "1") (pinfunction "1_1") (pintype "passive"))
      (node (ref "R10") (pin "1") (pinfunction "1_1") (pintype "passive"))
      (node (ref "R9") (pin "2") (pinfunction "2_2") (pintype "passive"))
      (node (ref "U3") (pin "4") (pinfunction "VC_4") (pintype "passive"))
    )
    (net (code "55") (name "Net-(U3-VDD)") (class "Default")
      (node (ref "C8") (pin "2") (pinfunction "2_2") (pintype "passive"))
      (node (ref "R7") (pin "1") (pinfunction "1_1") (pintype "passive"))
      (node (ref "U3") (pin "5") (pinfunction "VDD_5") (pintype "passive"))
    )
    (net (code "56") (name "Net-(U7-FB)") (class "Default")
      (node (ref "R2") (pin "2") (pinfunction "2_2") (pintype "passive"))
      (node (ref "R4") (pin "1") (pinfunction "1_1") (pintype "passive"))
      (node (ref "U7") (pin "3") (pinfunction "FB_3") (pintype "input"))
    )
    (net (code "57") (name "Net-(U10-RS)") (class "Default")
      (node (ref "R19") (pin "1") (pinfunction "1_1") (pintype "passive"))
      (node (ref "U10") (pin "7") (pinfunction "RS_7") (pintype "bidirectional"))
    )
    (net (code "58") (name "Net-(U11-RS)") (class "Default")
      (node (ref "R20") (pin "1") (pinfunction "1_1") (pintype "passive"))
      (node (ref "U11") (pin "7") (pinfunction "RS_7") (pintype "bidirectional"))
    )
    (net (code "59") (name "Net-(U12-RS)") (class "Default")
      (node (ref "R21") (pin "1") (pinfunction "1_1") (pintype "passive"))
      (node (ref "U12") (pin "7") (pinfunction "RS_7") (pintype "bidirectional"))
    )
    (net (code "60") (name "RTS") (class "Default")
      (node (ref "Q5") (pin "2") (pinfunction "E_2") (pintype "passive"))
      (node (ref "R17") (pin "1") (pinfunction "1_1") (pintype "passive"))
      (node (ref "U1") (pin "3") (pinfunction "~{RTS}_3") (pintype "output"))
    )
    (net (code "61") (name "USBDM") (class "Default")
      (node (ref "C10") (pin "2") (pinfunction "2_2") (pintype "passive"))
      (node (ref "R12") (pin "2") (pinfunction "2_2") (pintype "passive"))
      (node (ref "U1") (pin "16") (pinfunction "USBDM_16") (pintype "bidirectional"))
    )
    (net (code "62") (name "USBDP") (class "Default")
      (node (ref "C11") (pin "2") (pinfunction "2_2") (pintype "passive"))
      (node (ref "R13") (pin "2") (pinfunction "2_2") (pintype "passive"))
      (node (ref "U1") (pin "15") (pinfunction "USBDP_15") (pintype "bidirectional"))
    )
    (net (code "63") (name "VCC") (class "Default")
      (node (ref "C4") (pin "1") (pinfunction "1_1") (pintype "passive"))
      (node (ref "C5") (pin "1") (pinfunction "1_1") (pintype "passive"))
      (node (ref "C6") (pin "1") (pinfunction "1_1") (pintype "passive"))
      (node (ref "D3") (pin "1") (pinfunction "C_1") (pintype "passive"))
      (node (ref "LED1") (pin "1-VDD") (pinfunction "VDD_1-VDD") (pintype "power_in"))
      (node (ref "LED2") (pin "1-VDD") (pinfunction "VDD_1-VDD") (pintype "power_in"))
      (node (ref "LED3") (pin "1-VDD") (pinfunction "VDD_1-VDD") (pintype "power_in"))
      (node (ref "LED4") (pin "1-VDD") (pinfunction "VDD_1-VDD") (pintype "power_in"))
      (node (ref "LED5") (pin "1-VDD") (pinfunction "VDD_1-VDD") (pintype "power_in"))
      (node (ref "LED6") (pin "1-VDD") (pinfunction "VDD_1-VDD") (pintype "power_in"))
      (node (ref "REG1") (pin "P$3") (pinfunction "OUT_P$3") (pintype "bidirectional"))
      (node (ref "U8") (pin "1") (pinfunction "IN_1") (pintype "input"))
    )
    (net (code "64") (name "VIN") (class "Default")
      (node (ref "C1") (pin "1") (pinfunction "1_1") (pintype "passive"))
      (node (ref "C15") (pin "1") (pinfunction "1_1") (pintype "passive"))
      (node (ref "C17") (pin "1") (pinfunction "1_1") (pintype "passive"))
      (node (ref "C18") (pin "1") (pinfunction "1_1") (pintype "passive"))
      (node (ref "C2") (pin "1") (pinfunction "1_1") (pintype "passive"))
      (node (ref "C21") (pin "1") (pinfunction "1_1") (pintype "passive"))
      (node (ref "C22") (pin "1") (pinfunction "1_1") (pintype "passive"))
      (node (ref "C3") (pin "1") (pinfunction "1_1") (pintype "passive"))
      (node (ref "L1") (pin "2") (pinfunction "2_2") (pintype "passive"))
      (node (ref "R3") (pin "2") (pinfunction "2_2") (pintype "passive"))
      (node (ref "R7") (pin "2") (pinfunction "2_2") (pintype "passive"))
      (node (ref "R9") (pin "1") (pinfunction "1_1") (pintype "passive"))
      (node (ref "REG1") (pin "P$1") (pinfunction "IN_P$1") (pintype "bidirectional"))
      (node (ref "SW1") (pin "P$1") (pinfunction "A_P$1") (pintype "bidirectional"))
      (node (ref "U10") (pin "5") (pinfunction "VM_5") (pintype "bidirectional"))
      (node (ref "U11") (pin "5") (pinfunction "VM_5") (pintype "bidirectional"))
      (node (ref "U12") (pin "5") (pinfunction "VM_5") (pintype "bidirectional"))
      (node (ref "U7") (pin "4") (pinfunction "EN_4") (pintype "input"))
      (node (ref "U7") (pin "5") (pinfunction "IN_5") (pintype "input"))
    )
    (net (code "65") (name "VOLTAGE") (class "Default")
      (node (ref "R3") (pin "1") (pinfunction "1_1") (pintype "passive"))
      (node (ref "R5") (pin "2") (pinfunction "2_2") (pintype "passive"))
      (node (ref "U2") (pin "6") (pinfunction "IO34_6") (pintype "input"))
    )
    (net (code "66") (name "VUSB") (class "Default")
      (node (ref "D3") (pin "2") (pinfunction "A_2") (pintype "passive"))
      (node (ref "J1") (pin "VBUS") (pinfunction "VBUS_VBUS") (pintype "bidirectional"))
      (node (ref "U1") (pin "20") (pinfunction "VCC_20") (pintype "power_in"))
    )
    (net (code "67") (name "unconnected-(LED6-DO-Pad2-DOUT)") (class "Default")
      (node (ref "LED6") (pin "2-DOUT") (pinfunction "DO_2-DOUT") (pintype "output"))
    )
    (net (code "68") (name "unconnected-(SW1-B-PadP$3)") (class "Default")
      (node (ref "SW1") (pin "P$3") (pinfunction "B_P$3") (pintype "bidirectional"))
    )
    (net (code "69") (name "unconnected-(U1-CBUS0-Pad23)") (class "Default")
      (node (ref "U1") (pin "23") (pinfunction "CBUS0_23") (pintype "bidirectional"))
    )
    (net (code "70") (name "unconnected-(U1-CBUS1-Pad22)") (class "Default")
      (node (ref "U1") (pin "22") (pinfunction "CBUS1_22") (pintype "bidirectional"))
    )
    (net (code "71") (name "unconnected-(U1-CBUS2-Pad13)") (class "Default")
      (node (ref "U1") (pin "13") (pinfunction "CBUS2_13") (pintype "bidirectional"))
    )
    (net (code "72") (name "unconnected-(U1-CBUS3-Pad14)") (class "Default")
      (node (ref "U1") (pin "14") (pinfunction "CBUS3_14") (pintype "bidirectional"))
    )
    (net (code "73") (name "unconnected-(U1-CBUS4-Pad12)") (class "Default")
      (node (ref "U1") (pin "12") (pinfunction "CBUS4_12") (pintype "bidirectional"))
    )
    (net (code "74") (name "unconnected-(U1-OSCI-Pad27)") (class "Default")
      (node (ref "U1") (pin "27") (pinfunction "OSCI_27") (pintype "input"))
    )
    (net (code "75") (name "unconnected-(U1-OSCO-Pad28)") (class "Default")
      (node (ref "U1") (pin "28") (pinfunction "OSCO_28") (pintype "output"))
    )
    (net (code "76") (name "unconnected-(U1-~{CTS}-Pad11)") (class "Default")
      (node (ref "U1") (pin "11") (pinfunction "~{CTS}_11") (pintype "input"))
    )
    (net (code "77") (name "unconnected-(U1-~{DCD}-Pad10)") (class "Default")
      (node (ref "U1") (pin "10") (pinfunction "~{DCD}_10") (pintype "input"))
    )
    (net (code "78") (name "unconnected-(U1-~{DSR}-Pad9)") (class "Default")
      (node (ref "U1") (pin "9") (pinfunction "~{DSR}_9") (pintype "input"))
    )
    (net (code "79") (name "unconnected-(U1-~{RESET}-Pad19)") (class "Default")
      (node (ref "U1") (pin "19") (pinfunction "~{RESET}_19") (pintype "input"))
    )
    (net (code "80") (name "unconnected-(U1-~{RI}-Pad6)") (class "Default")
      (node (ref "U1") (pin "6") (pinfunction "~{RI}_6") (pintype "input"))
    )
    (net (code "81") (name "unconnected-(U2-IO2-Pad24)") (class "Default")
      (node (ref "U2") (pin "24") (pinfunction "IO2_24") (pintype "bidirectional"))
    )
    (net (code "82") (name "unconnected-(U2-IO5-Pad29)") (class "Default")
      (node (ref "U2") (pin "29") (pinfunction "IO5_29") (pintype "bidirectional"))
    )
    (net (code "83") (name "unconnected-(U2-IO12-Pad14)") (class "Default")
      (node (ref "U2") (pin "14") (pinfunction "IO12_14") (pintype "bidirectional"))
    )
    (net (code "84") (name "unconnected-(U2-IO15-Pad23)") (class "Default")
      (node (ref "U2") (pin "23") (pinfunction "IO15_23") (pintype "bidirectional"))
    )
    (net (code "85") (name "unconnected-(U2-IO35-Pad7)") (class "Default")
      (node (ref "U2") (pin "7") (pinfunction "IO35_7") (pintype "input"))
    )
    (net (code "86") (name "unconnected-(U2-NC-Pad17)") (class "Default")
      (node (ref "U2") (pin "17") (pinfunction "NC_17") (pintype "no_connect"))
    )
    (net (code "87") (name "unconnected-(U2-NC-Pad18)") (class "Default")
      (node (ref "U2") (pin "18") (pinfunction "NC_18") (pintype "no_connect"))
    )
    (net (code "88") (name "unconnected-(U2-NC-Pad19)") (class "Default")
      (node (ref "U2") (pin "19") (pinfunction "NC_19") (pintype "no_connect"))
    )
    (net (code "89") (name "unconnected-(U2-NC-Pad20)") (class "Default")
      (node (ref "U2") (pin "20") (pinfunction "NC_20") (pintype "no_connect"))
    )
    (net (code "90") (name "unconnected-(U2-NC-Pad21)") (class "Default")
      (node (ref "U2") (pin "21") (pinfunction "NC_21") (pintype "no_connect"))
    )
    (net (code "91") (name "unconnected-(U2-NC-Pad22)") (class "Default")
      (node (ref "U2") (pin "22") (pinfunction "NC_22") (pintype "no_connect"))
    )
    (net (code "92") (name "unconnected-(U2-NC1-Pad32)") (class "Default")
      (node (ref "U2") (pin "32") (pinfunction "NC1_32") (pintype "no_connect"))
    )
    (net (code "93") (name "unconnected-(U2-SENSOR_VN-Pad5)") (class "Default")
      (node (ref "U2") (pin "5") (pinfunction "SENSOR_VN_5") (pintype "input"))
    )
    (net (code "94") (name "unconnected-(U2-SENSOR_VP-Pad4)") (class "Default")
      (node (ref "U2") (pin "4") (pinfunction "SENSOR_VP_4") (pintype "input"))
    )
  )
)
